# design.net
KiCad netlist of a schematic drawn in Altium Designer
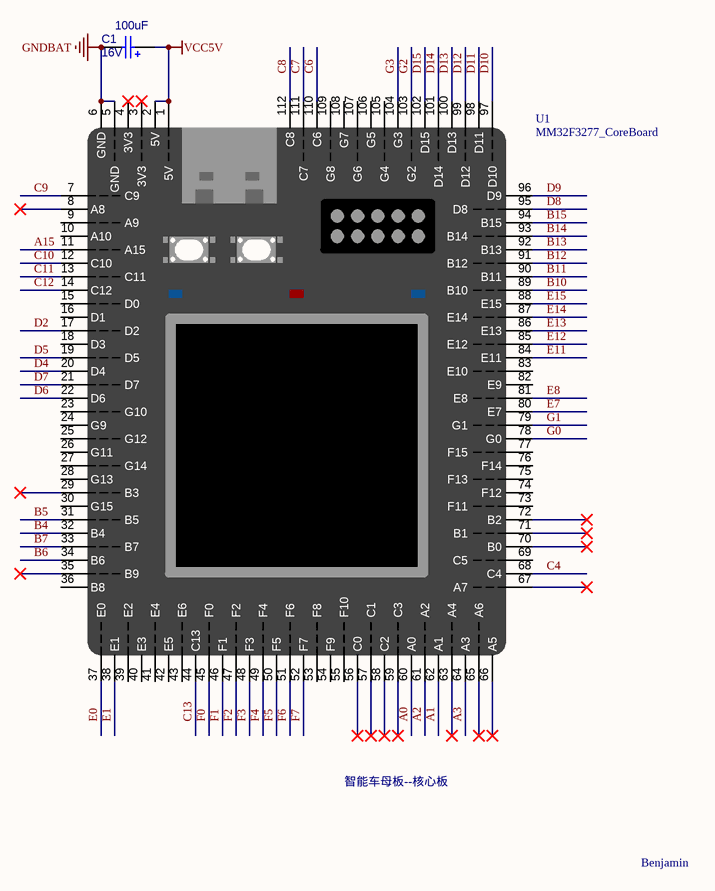
[diagram p0: 核心板.SchDoc]

(export (version "E")
  (design (tool "Eeschema 10.0.6"))
  (components
    (comp (ref "C1")
      (value "100uF")
      (footprint "CAPT3528")
      (description "Tantalum Capacitor")
      (fields
        (field (name "VOLTAGE") "16V")
        (field (name "Comment") "100uF 16V")
        (field (name "PUBLISHER") "Altium Limited")
      )
      (libsource (lib "MM32F3277主板原理图库") (part "Cap-Tan"))
    )
    (comp (ref "U1")
      (value "MM32F3277_CoreBoard")
      (footprint "MM32F3277_CoreBoard")
      (description "逐飞科技MM32F3277核心板")
      (libsource (lib "MM32F3277核心板整体原理") (part "MM32F3277_CoreBoard"))
    )
  )
  (nets
    (net (code "1") (name "/A0") (class "Default")
      (node (ref "U1") (pin "60") (pinfunction "A0_60") (pintype "passive"))
    )
    (net (code "2") (name "/A1") (class "Default")
      (node (ref "U1") (pin "62") (pinfunction "A1_62") (pintype "passive"))
    )
    (net (code "3") (name "/A2") (class "Default")
      (node (ref "U1") (pin "61") (pinfunction "A2_61") (pintype "passive"))
    )
    (net (code "4") (name "/A3") (class "Default")
      (node (ref "U1") (pin "64") (pinfunction "A3_64") (pintype "passive"))
    )
    (net (code "5") (name "/A15") (class "Default")
      (node (ref "U1") (pin "11") (pinfunction "A15_11") (pintype "passive"))
    )
    (net (code "6") (name "/B4") (class "Default")
      (node (ref "U1") (pin "32") (pinfunction "B4_32") (pintype "passive"))
    )
    (net (code "7") (name "/B5") (class "Default")
      (node (ref "U1") (pin "31") (pinfunction "B5_31") (pintype "passive"))
    )
    (net (code "8") (name "/B6") (class "Default")
      (node (ref "U1") (pin "34") (pinfunction "B6_34") (pintype "passive"))
    )
    (net (code "9") (name "/B7") (class "Default")
      (node (ref "U1") (pin "33") (pinfunction "B7_33") (pintype "passive"))
    )
    (net (code "10") (name "/B10") (class "Default")
      (node (ref "U1") (pin "89") (pinfunction "B10_89") (pintype "passive"))
    )
    (net (code "11") (name "/B11") (class "Default")
      (node (ref "U1") (pin "90") (pinfunction "B11_90") (pintype "passive"))
    )
    (net (code "12") (name "/B12") (class "Default")
      (node (ref "U1") (pin "91") (pinfunction "B12_91") (pintype "passive"))
    )
    (net (code "13") (name "/B13") (class "Default")
      (node (ref "U1") (pin "92") (pinfunction "B13_92") (pintype "passive"))
    )
    (net (code "14") (name "/B14") (class "Default")
      (node (ref "U1") (pin "93") (pinfunction "B14_93") (pintype "passive"))
    )
    (net (code "15") (name "/B15") (class "Default")
      (node (ref "U1") (pin "94") (pinfunction "B15_94") (pintype "passive"))
    )
    (net (code "16") (name "/C4") (class "Default")
      (node (ref "U1") (pin "68") (pinfunction "C4_68") (pintype "passive"))
    )
    (net (code "17") (name "/C6") (class "Default")
      (node (ref "U1") (pin "110") (pinfunction "C6_110") (pintype "passive"))
    )
    (net (code "18") (name "/C7") (class "Default")
      (node (ref "U1") (pin "111") (pinfunction "C7_111") (pintype "passive"))
    )
    (net (code "19") (name "/C8") (class "Default")
      (node (ref "U1") (pin "112") (pinfunction "C8_112") (pintype "passive"))
    )
    (net (code "20") (name "/C9") (class "Default")
      (node (ref "U1") (pin "7") (pinfunction "C9_7") (pintype "passive"))
    )
    (net (code "21") (name "/C10") (class "Default")
      (node (ref "U1") (pin "12") (pinfunction "C10_12") (pintype "passive"))
    )
    (net (code "22") (name "/C11") (class "Default")
      (node (ref "U1") (pin "13") (pinfunction "C11_13") (pintype "passive"))
    )
    (net (code "23") (name "/C12") (class "Default")
      (node (ref "U1") (pin "14") (pinfunction "C12_14") (pintype "passive"))
    )
    (net (code "24") (name "/C13") (class "Default")
      (node (ref "U1") (pin "44") (pinfunction "C13_44") (pintype "passive"))
    )
    (net (code "25") (name "/D2") (class "Default")
      (node (ref "U1") (pin "17") (pinfunction "D2_17") (pintype "passive"))
    )
    (net (code "26") (name "/D4") (class "Default")
      (node (ref "U1") (pin "20") (pinfunction "D4_20") (pintype "passive"))
    )
    (net (code "27") (name "/D5") (class "Default")
      (node (ref "U1") (pin "19") (pinfunction "D5_19") (pintype "passive"))
    )
    (net (code "28") (name "/D6") (class "Default")
      (node (ref "U1") (pin "22") (pinfunction "D6_22") (pintype "passive"))
    )
    (net (code "29") (name "/D7") (class "Default")
      (node (ref "U1") (pin "21") (pinfunction "D7_21") (pintype "passive"))
    )
    (net (code "30") (name "/D8") (class "Default")
      (node (ref "U1") (pin "95") (pinfunction "D8_95") (pintype "passive"))
    )
    (net (code "31") (name "/D9") (class "Default")
      (node (ref "U1") (pin "96") (pinfunction "D9_96") (pintype "passive"))
    )
    (net (code "32") (name "/D10") (class "Default")
      (node (ref "U1") (pin "97") (pinfunction "D10_97") (pintype "passive"))
    )
    (net (code "33") (name "/D11") (class "Default")
      (node (ref "U1") (pin "98") (pinfunction "D11_98") (pintype "passive"))
    )
    (net (code "34") (name "/D12") (class "Default")
      (node (ref "U1") (pin "99") (pinfunction "D12_99") (pintype "passive"))
    )
    (net (code "35") (name "/D13") (class "Default")
      (node (ref "U1") (pin "100") (pinfunction "D13_100") (pintype "passive"))
    )
    (net (code "36") (name "/D14") (class "Default")
      (node (ref "U1") (pin "101") (pinfunction "D14_101") (pintype "passive"))
    )
    (net (code "37") (name "/D15") (class "Default")
      (node (ref "U1") (pin "102") (pinfunction "D15_102") (pintype "passive"))
    )
    (net (code "38") (name "/E0") (class "Default")
      (node (ref "U1") (pin "37") (pinfunction "E0_37") (pintype "passive"))
    )
    (net (code "39") (name "/E1") (class "Default")
      (node (ref "U1") (pin "38") (pinfunction "E1_38") (pintype "passive"))
    )
    (net (code "40") (name "/E7") (class "Default")
      (node (ref "U1") (pin "80") (pinfunction "E7_80") (pintype "passive"))
    )
    (net (code "41") (name "/E8") (class "Default")
      (node (ref "U1") (pin "81") (pinfunction "E8_81") (pintype "passive"))
    )
    (net (code "42") (name "/E11") (class "Default")
      (node (ref "U1") (pin "84") (pinfunction "E11_84") (pintype "passive"))
    )
    (net (code "43") (name "/E12") (class "Default")
      (node (ref "U1") (pin "85") (pinfunction "E12_85") (pintype "passive"))
    )
    (net (code "44") (name "/E13") (class "Default")
      (node (ref "U1") (pin "86") (pinfunction "E13_86") (pintype "passive"))
    )
    (net (code "45") (name "/E14") (class "Default")
      (node (ref "U1") (pin "87") (pinfunction "E14_87") (pintype "passive"))
    )
    (net (code "46") (name "/E15") (class "Default")
      (node (ref "U1") (pin "88") (pinfunction "E15_88") (pintype "passive"))
    )
    (net (code "47") (name "/F0") (class "Default")
      (node (ref "U1") (pin "45") (pinfunction "F0_45") (pintype "passive"))
    )
    (net (code "48") (name "/F1") (class "Default")
      (node (ref "U1") (pin "46") (pinfunction "F1_46") (pintype "passive"))
    )
    (net (code "49") (name "/F2") (class "Default")
      (node (ref "U1") (pin "47") (pinfunction "F2_47") (pintype "passive"))
    )
    (net (code "50") (name "/F3") (class "Default")
      (node (ref "U1") (pin "48") (pinfunction "F3_48") (pintype "passive"))
    )
    (net (code "51") (name "/F4") (class "Default")
      (node (ref "U1") (pin "49") (pinfunction "F4_49") (pintype "passive"))
    )
    (net (code "52") (name "/F5") (class "Default")
      (node (ref "U1") (pin "50") (pinfunction "F5_50") (pintype "passive"))
    )
    (net (code "53") (name "/F6") (class "Default")
      (node (ref "U1") (pin "51") (pinfunction "F6_51") (pintype "passive"))
    )
    (net (code "54") (name "/F7") (class "Default")
      (node (ref "U1") (pin "52") (pinfunction "F7_52") (pintype "passive"))
    )
    (net (code "55") (name "/G0") (class "Default")
      (node (ref "U1") (pin "78") (pinfunction "G0_78") (pintype "passive"))
    )
    (net (code "56") (name "/G1") (class "Default")
      (node (ref "U1") (pin "79") (pinfunction "G1_79") (pintype "passive"))
    )
    (net (code "57") (name "/G2") (class "Default")
      (node (ref "U1") (pin "103") (pinfunction "G2_103") (pintype "passive"))
    )
    (net (code "58") (name "/G3") (class "Default")
      (node (ref "U1") (pin "104") (pinfunction "G3_104") (pintype "passive"))
    )
    (net (code "59") (name "GNDBAT") (class "Default")
      (node (ref "C1") (pin "2") (pinfunction "2_2") (pintype "passive"))
      (node (ref "U1") (pin "5") (pinfunction "GND_5") (pintype "passive"))
      (node (ref "U1") (pin "6") (pinfunction "GND_6") (pintype "passive"))
    )
    (net (code "60") (name "VCC5V") (class "Default")
      (node (ref "C1") (pin "1") (pinfunction "1_1") (pintype "passive"))
      (node (ref "U1") (pin "1") (pinfunction "5V_1") (pintype "passive"))
      (node (ref "U1") (pin "2") (pinfunction "5V_2") (pintype "passive"))
    )
    (net (code "61") (name "unconnected-(U1-3V3-Pad3)") (class "Default")
      (node (ref "U1") (pin "3") (pinfunction "3V3_3") (pintype "passive+no_connect"))
    )
    (net (code "62") (name "unconnected-(U1-3V3-Pad4)") (class "Default")
      (node (ref "U1") (pin "4") (pinfunction "3V3_4") (pintype "passive+no_connect"))
    )
    (net (code "63") (name "unconnected-(U1-A4-Pad63)") (class "Default")
      (node (ref "U1") (pin "63") (pinfunction "A4_63") (pintype "passive+no_connect"))
    )
    (net (code "64") (name "unconnected-(U1-A5-Pad66)") (class "Default")
      (node (ref "U1") (pin "66") (pinfunction "A5_66") (pintype "passive+no_connect"))
    )
    (net (code "65") (name "unconnected-(U1-A6-Pad65)") (class "Default")
      (node (ref "U1") (pin "65") (pinfunction "A6_65") (pintype "passive+no_connect"))
    )
    (net (code "66") (name "unconnected-(U1-A7-Pad67)") (class "Default")
      (node (ref "U1") (pin "67") (pinfunction "A7_67") (pintype "passive+no_connect"))
    )
    (net (code "67") (name "unconnected-(U1-A8-Pad8)") (class "Default")
      (node (ref "U1") (pin "8") (pinfunction "A8_8") (pintype "passive+no_connect"))
    )
    (net (code "68") (name "unconnected-(U1-A9-Pad9)") (class "Default")
      (node (ref "U1") (pin "9") (pinfunction "A9_9") (pintype "passive"))
    )
    (net (code "69") (name "unconnected-(U1-A10-Pad10)") (class "Default")
      (node (ref "U1") (pin "10") (pinfunction "A10_10") (pintype "passive"))
    )
    (net (code "70") (name "unconnected-(U1-B0-Pad70)") (class "Default")
      (node (ref "U1") (pin "70") (pinfunction "B0_70") (pintype "passive+no_connect"))
    )
    (net (code "71") (name "unconnected-(U1-B1-Pad71)") (class "Default")
      (node (ref "U1") (pin "71") (pinfunction "B1_71") (pintype "passive+no_connect"))
    )
    (net (code "72") (name "unconnected-(U1-B2-Pad72)") (class "Default")
      (node (ref "U1") (pin "72") (pinfunction "B2_72") (pintype "passive+no_connect"))
    )
    (net (code "73") (name "unconnected-(U1-B3-Pad29)") (class "Default")
      (node (ref "U1") (pin "29") (pinfunction "B3_29") (pintype "passive+no_connect"))
    )
    (net (code "74") (name "unconnected-(U1-B8-Pad36)") (class "Default")
      (node (ref "U1") (pin "36") (pinfunction "B8_36") (pintype "passive"))
    )
    (net (code "75") (name "unconnected-(U1-B9-Pad35)") (class "Default")
      (node (ref "U1") (pin "35") (pinfunction "B9_35") (pintype "passive+no_connect"))
    )
    (net (code "76") (name "unconnected-(U1-C0-Pad56)") (class "Default")
      (node (ref "U1") (pin "56") (pinfunction "C0_56") (pintype "passive+no_connect"))
    )
    (net (code "77") (name "unconnected-(U1-C1-Pad57)") (class "Default")
      (node (ref "U1") (pin "57") (pinfunction "C1_57") (pintype "passive+no_connect"))
    )
    (net (code "78") (name "unconnected-(U1-C2-Pad58)") (class "Default")
      (node (ref "U1") (pin "58") (pinfunction "C2_58") (pintype "passive+no_connect"))
    )
    (net (code "79") (name "unconnected-(U1-C3-Pad59)") (class "Default")
      (node (ref "U1") (pin "59") (pinfunction "C3_59") (pintype "passive+no_connect"))
    )
    (net (code "80") (name "unconnected-(U1-C5-Pad69)") (class "Default")
      (node (ref "U1") (pin "69") (pinfunction "C5_69") (pintype "passive"))
    )
    (net (code "81") (name "unconnected-(U1-D0-Pad15)") (class "Default")
      (node (ref "U1") (pin "15") (pinfunction "D0_15") (pintype "passive"))
    )
    (net (code "82") (name "unconnected-(U1-D1-Pad16)") (class "Default")
      (node (ref "U1") (pin "16") (pinfunction "D1_16") (pintype "passive"))
    )
    (net (code "83") (name "unconnected-(U1-D3-Pad18)") (class "Default")
      (node (ref "U1") (pin "18") (pinfunction "D3_18") (pintype "passive"))
    )
    (net (code "84") (name "unconnected-(U1-E2-Pad39)") (class "Default")
      (node (ref "U1") (pin "39") (pinfunction "E2_39") (pintype "passive"))
    )
    (net (code "85") (name "unconnected-(U1-E3-Pad40)") (class "Default")
      (node (ref "U1") (pin "40") (pinfunction "E3_40") (pintype "passive"))
    )
    (net (code "86") (name "unconnected-(U1-E4-Pad41)") (class "Default")
      (node (ref "U1") (pin "41") (pinfunction "E4_41") (pintype "passive"))
    )
    (net (code "87") (name "unconnected-(U1-E5-Pad42)") (class "Default")
      (node (ref "U1") (pin "42") (pinfunction "E5_42") (pintype "passive"))
    )
    (net (code "88") (name "unconnected-(U1-E6-Pad43)") (class "Default")
      (node (ref "U1") (pin "43") (pinfunction "E6_43") (pintype "passive"))
    )
    (net (code "89") (name "unconnected-(U1-E9-Pad82)") (class "Default")
      (node (ref "U1") (pin "82") (pinfunction "E9_82") (pintype "passive"))
    )
    (net (code "90") (name "unconnected-(U1-E10-Pad83)") (class "Default")
      (node (ref "U1") (pin "83") (pinfunction "E10_83") (pintype "passive"))
    )
    (net (code "91") (name "unconnected-(U1-F8-Pad53)") (class "Default")
      (node (ref "U1") (pin "53") (pinfunction "F8_53") (pintype "passive"))
    )
    (net (code "92") (name "unconnected-(U1-F9-Pad54)") (class "Default")
      (node (ref "U1") (pin "54") (pinfunction "F9_54") (pintype "passive"))
    )
    (net (code "93") (name "unconnected-(U1-F10-Pad55)") (class "Default")
      (node (ref "U1") (pin "55") (pinfunction "F10_55") (pintype "passive"))
    )
    (net (code "94") (name "unconnected-(U1-F11-Pad73)") (class "Default")
      (node (ref "U1") (pin "73") (pinfunction "F11_73") (pintype "passive"))
    )
    (net (code "95") (name "unconnected-(U1-F12-Pad74)") (class "Default")
      (node (ref "U1") (pin "74") (pinfunction "F12_74") (pintype "passive"))
    )
    (net (code "96") (name "unconnected-(U1-F13-Pad75)") (class "Default")
      (node (ref "U1") (pin "75") (pinfunction "F13_75") (pintype "passive"))
    )
    (net (code "97") (name "unconnected-(U1-F14-Pad76)") (class "Default")
      (node (ref "U1") (pin "76") (pinfunction "F14_76") (pintype "passive"))
    )
    (net (code "98") (name "unconnected-(U1-F15-Pad77)") (class "Default")
      (node (ref "U1") (pin "77") (pinfunction "F15_77") (pintype "passive"))
    )
    (net (code "99") (name "unconnected-(U1-G4-Pad105)") (class "Default")
      (node (ref "U1") (pin "105") (pinfunction "G4_105") (pintype "passive"))
    )
    (net (code "100") (name "unconnected-(U1-G5-Pad106)") (class "Default")
      (node (ref "U1") (pin "106") (pinfunction "G5_106") (pintype "passive"))
    )
    (net (code "101") (name "unconnected-(U1-G6-Pad107)") (class "Default")
      (node (ref "U1") (pin "107") (pinfunction "G6_107") (pintype "passive"))
    )
    (net (code "102") (name "unconnected-(U1-G7-Pad108)") (class "Default")
      (node (ref "U1") (pin "108") (pinfunction "G7_108") (pintype "passive"))
    )
    (net (code "103") (name "unconnected-(U1-G8-Pad109)") (class "Default")
      (node (ref "U1") (pin "109") (pinfunction "G8_109") (pintype "passive"))
    )
    (net (code "104") (name "unconnected-(U1-G9-Pad24)") (class "Default")
      (node (ref "U1") (pin "24") (pinfunction "G9_24") (pintype "passive"))
    )
    (net (code "105") (name "unconnected-(U1-G10-Pad23)") (class "Default")
      (node (ref "U1") (pin "23") (pinfunction "G10_23") (pintype "passive"))
    )
    (net (code "106") (name "unconnected-(U1-G11-Pad26)") (class "Default")
      (node (ref "U1") (pin "26") (pinfunction "G11_26") (pintype "passive"))
    )
    (net (code "107") (name "unconnected-(U1-G12-Pad25)") (class "Default")
      (node (ref "U1") (pin "25") (pinfunction "G12_25") (pintype "passive"))
    )
    (net (code "108") (name "unconnected-(U1-G13-Pad28)") (class "Default")
      (node (ref "U1") (pin "28") (pinfunction "G13_28") (pintype "passive"))
    )
    (net (code "109") (name "unconnected-(U1-G14-Pad27)") (class "Default")
      (node (ref "U1") (pin "27") (pinfunction "G14_27") (pintype "passive"))
    )
    (net (code "110") (name "unconnected-(U1-G15-Pad30)") (class "Default")
      (node (ref "U1") (pin "30") (pinfunction "G15_30") (pintype "passive"))
    )
  )
)
